# Sensor_Board.net
KiCad netlist of a schematic drawn in EAGLE
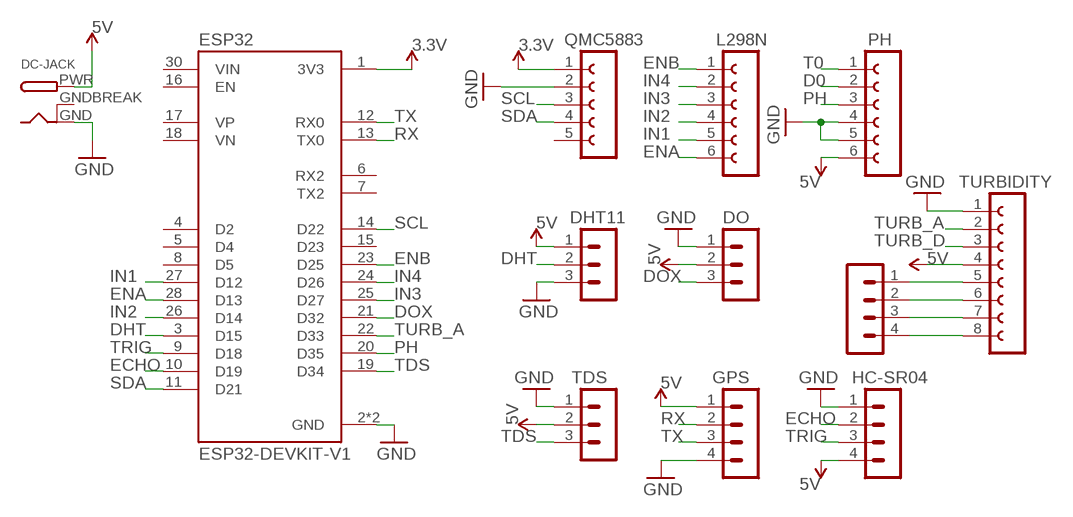
[diagram p0: schematic, sheet 1]

(export (version "E")
  (design (tool "Eeschema 10.0.6"))
  (components
    (comp (ref "DC-JACK")
      (value "DCBARRELPTH")
      (footprint "eagle-import:DCJACK_2MM_PTH")
      (libsource (lib "eagle-import") (part "DCBARRELPTH"))
    )
    (comp (ref "DHT11")
      (value "MA03-1")
      (footprint "eagle-import:MA03-1")
      (libsource (lib "eagle-import") (part "MA03-1"))
    )
    (comp (ref "DO")
      (value "MA03-1")
      (footprint "eagle-import:MA03-1")
      (libsource (lib "eagle-import") (part "MA03-1"))
    )
    (comp (ref "ESP32")
      (value "ESP32-DEVKIT-V1")
      (footprint "eagle-import:MODULE_ESP32_DEVKIT_V1")
      (fields (field (name "MF") "Do it"))
      (libsource (lib "eagle-import") (part "ESP32-DEVKIT-V1"))
    )
    (comp (ref "GPS")
      (value "MA04-1")
      (footprint "eagle-import:MA04-1")
      (libsource (lib "eagle-import") (part "MA04-1"))
    )
    (comp (ref "HC-SR04")
      (value "MA04-1")
      (footprint "eagle-import:MA04-1")
      (libsource (lib "eagle-import") (part "MA04-1"))
    )
    (comp (ref "L298N")
      (value "FE06-1")
      (footprint "eagle-import:FE06")
      (libsource (lib "eagle-import") (part "FE06-1"))
    )
    (comp (ref "PH")
      (value "FE06-1")
      (footprint "eagle-import:FE06")
      (libsource (lib "eagle-import") (part "FE06-1"))
    )
    (comp (ref "QMC5883")
      (value "FE05W")
      (footprint "eagle-import:FE05W")
      (libsource (lib "eagle-import") (part "FE05W"))
    )
    (comp (ref "SV10")
      (value "MA04-1")
      (footprint "eagle-import:MA04-1")
      (libsource (lib "eagle-import") (part "MA04-1"))
    )
    (comp (ref "TDS")
      (value "MA03-1")
      (footprint "eagle-import:MA03-1")
      (libsource (lib "eagle-import") (part "MA03-1"))
    )
    (comp (ref "TURBIDITY")
      (value "FE08-1")
      (footprint "eagle-import:FE08")
      (libsource (lib "eagle-import") (part "FE08-1"))
    )
  )
  (nets
    (net (code "1") (name "/D0") (class "Default")
      (node (ref "PH") (pin "2") (pinfunction "2_2") (pintype "passive"))
    )
    (net (code "2") (name "/DHT") (class "Default")
      (node (ref "DHT11") (pin "2") (pinfunction "2_2") (pintype "passive"))
      (node (ref "ESP32") (pin "3") (pinfunction "D15_3") (pintype "bidirectional"))
    )
    (net (code "3") (name "/DOX") (class "Default")
      (node (ref "DO") (pin "3") (pinfunction "3_3") (pintype "passive"))
      (node (ref "ESP32") (pin "21") (pinfunction "D32_21") (pintype "bidirectional"))
    )
    (net (code "4") (name "/ECHO") (class "Default")
      (node (ref "ESP32") (pin "10") (pinfunction "D19_10") (pintype "bidirectional"))
      (node (ref "HC-SR04") (pin "2") (pinfunction "2_2") (pintype "passive"))
    )
    (net (code "5") (name "/ENA") (class "Default")
      (node (ref "ESP32") (pin "28") (pinfunction "D13_28") (pintype "bidirectional"))
      (node (ref "L298N") (pin "6") (pinfunction "6_6") (pintype "passive"))
    )
    (net (code "6") (name "/ENB") (class "Default")
      (node (ref "ESP32") (pin "23") (pinfunction "D25_23") (pintype "bidirectional"))
      (node (ref "L298N") (pin "1") (pinfunction "1_1") (pintype "passive"))
    )
    (net (code "7") (name "/GNDBREAK") (class "Default")
      (node (ref "DC-JACK") (pin "GNDBREAK") (pinfunction "GNDBREAK_GNDBREAK") (pintype "power_in"))
    )
    (net (code "8") (name "/IN1") (class "Default")
      (node (ref "ESP32") (pin "27") (pinfunction "D12_27") (pintype "bidirectional"))
      (node (ref "L298N") (pin "5") (pinfunction "5_5") (pintype "passive"))
    )
    (net (code "9") (name "/IN2") (class "Default")
      (node (ref "ESP32") (pin "26") (pinfunction "D14_26") (pintype "bidirectional"))
      (node (ref "L298N") (pin "4") (pinfunction "4_4") (pintype "passive"))
    )
    (net (code "10") (name "/IN3") (class "Default")
      (node (ref "ESP32") (pin "25") (pinfunction "D27_25") (pintype "bidirectional"))
      (node (ref "L298N") (pin "3") (pinfunction "3_3") (pintype "passive"))
    )
    (net (code "11") (name "/IN4") (class "Default")
      (node (ref "ESP32") (pin "24") (pinfunction "D26_24") (pintype "bidirectional"))
      (node (ref "L298N") (pin "2") (pinfunction "2_2") (pintype "passive"))
    )
    (net (code "12") (name "/PH") (class "Default")
      (node (ref "ESP32") (pin "20") (pinfunction "D35_20") (pintype "bidirectional"))
      (node (ref "PH") (pin "3") (pinfunction "3_3") (pintype "passive"))
    )
    (net (code "13") (name "/RX") (class "Default")
      (node (ref "ESP32") (pin "13") (pinfunction "TX0_13") (pintype "output"))
      (node (ref "GPS") (pin "2") (pinfunction "2_2") (pintype "passive"))
    )
    (net (code "14") (name "/SCL") (class "Default")
      (node (ref "ESP32") (pin "14") (pinfunction "D22_14") (pintype "bidirectional"))
      (node (ref "QMC5883") (pin "3") (pinfunction "3_3") (pintype "passive"))
    )
    (net (code "15") (name "/SDA") (class "Default")
      (node (ref "ESP32") (pin "11") (pinfunction "D21_11") (pintype "bidirectional"))
      (node (ref "QMC5883") (pin "4") (pinfunction "4_4") (pintype "passive"))
    )
    (net (code "16") (name "/T0") (class "Default")
      (node (ref "PH") (pin "1") (pinfunction "1_1") (pintype "passive"))
    )
    (net (code "17") (name "/TDS") (class "Default")
      (node (ref "ESP32") (pin "19") (pinfunction "D34_19") (pintype "bidirectional"))
      (node (ref "TDS") (pin "3") (pinfunction "3_3") (pintype "passive"))
    )
    (net (code "18") (name "/TRIG") (class "Default")
      (node (ref "ESP32") (pin "9") (pinfunction "D18_9") (pintype "bidirectional"))
      (node (ref "HC-SR04") (pin "3") (pinfunction "3_3") (pintype "passive"))
    )
    (net (code "19") (name "/TURB_A") (class "Default")
      (node (ref "ESP32") (pin "22") (pinfunction "D33_22") (pintype "bidirectional"))
      (node (ref "TURBIDITY") (pin "2") (pinfunction "2_2") (pintype "passive"))
    )
    (net (code "20") (name "/TURB_D") (class "Default")
      (node (ref "TURBIDITY") (pin "3") (pinfunction "3_3") (pintype "passive"))
    )
    (net (code "21") (name "/TX") (class "Default")
      (node (ref "ESP32") (pin "12") (pinfunction "RX0_12") (pintype "input"))
      (node (ref "GPS") (pin "3") (pinfunction "3_3") (pintype "passive"))
    )
    (net (code "22") (name "GND") (class "Default")
      (node (ref "DC-JACK") (pin "GND") (pinfunction "GND_GND") (pintype "power_in"))
      (node (ref "DHT11") (pin "3") (pinfunction "3_3") (pintype "passive"))
      (node (ref "DO") (pin "1") (pinfunction "1_1") (pintype "passive"))
      (node (ref "ESP32") (pin "2") (pinfunction "GND_2") (pintype "power_in"))
      (node (ref "ESP32") (pin "29") (pinfunction "GND_29") (pintype "power_in"))
      (node (ref "GPS") (pin "4") (pinfunction "4_4") (pintype "passive"))
      (node (ref "HC-SR04") (pin "1") (pinfunction "1_1") (pintype "passive"))
      (node (ref "PH") (pin "4") (pinfunction "4_4") (pintype "passive"))
      (node (ref "PH") (pin "5") (pinfunction "5_5") (pintype "passive"))
      (node (ref "QMC5883") (pin "2") (pinfunction "2_2") (pintype "passive"))
      (node (ref "TDS") (pin "1") (pinfunction "1_1") (pintype "passive"))
      (node (ref "TURBIDITY") (pin "1") (pinfunction "1_1") (pintype "passive"))
    )
    (net (code "23") (name "Net-(SV10-Pad1)") (class "Default")
      (node (ref "SV10") (pin "1") (pinfunction "1_1") (pintype "passive"))
      (node (ref "TURBIDITY") (pin "5") (pinfunction "5_5") (pintype "passive"))
    )
    (net (code "24") (name "Net-(SV10-Pad2)") (class "Default")
      (node (ref "SV10") (pin "2") (pinfunction "2_2") (pintype "passive"))
      (node (ref "TURBIDITY") (pin "6") (pinfunction "6_6") (pintype "passive"))
    )
    (net (code "25") (name "Net-(SV10-Pad3)") (class "Default")
      (node (ref "SV10") (pin "3") (pinfunction "3_3") (pintype "passive"))
      (node (ref "TURBIDITY") (pin "7") (pinfunction "7_7") (pintype "passive"))
    )
    (net (code "26") (name "Net-(SV10-Pad4)") (class "Default")
      (node (ref "SV10") (pin "4") (pinfunction "4_4") (pintype "passive"))
      (node (ref "TURBIDITY") (pin "8") (pinfunction "8_8") (pintype "passive"))
    )
    (net (code "27") (name "VCC_1") (class "Default")
      (node (ref "DC-JACK") (pin "PWR") (pinfunction "PWR_PWR") (pintype "power_in"))
      (node (ref "DHT11") (pin "1") (pinfunction "1_1") (pintype "passive"))
      (node (ref "DO") (pin "2") (pinfunction "2_2") (pintype "passive"))
      (node (ref "GPS") (pin "1") (pinfunction "1_1") (pintype "passive"))
      (node (ref "HC-SR04") (pin "4") (pinfunction "4_4") (pintype "passive"))
      (node (ref "PH") (pin "6") (pinfunction "6_6") (pintype "passive"))
      (node (ref "TDS") (pin "2") (pinfunction "2_2") (pintype "passive"))
      (node (ref "TURBIDITY") (pin "4") (pinfunction "4_4") (pintype "passive"))
    )
    (net (code "28") (name "VCC_2") (class "Default")
      (node (ref "ESP32") (pin "1") (pinfunction "3V3_1") (pintype "output"))
      (node (ref "QMC5883") (pin "1") (pinfunction "1_1") (pintype "passive"))
    )
    (net (code "29") (name "unconnected-(ESP32-D2-Pad4)") (class "Default")
      (node (ref "ESP32") (pin "4") (pinfunction "D2_4") (pintype "bidirectional"))
    )
    (net (code "30") (name "unconnected-(ESP32-D4-Pad5)") (class "Default")
      (node (ref "ESP32") (pin "5") (pinfunction "D4_5") (pintype "bidirectional"))
    )
    (net (code "31") (name "unconnected-(ESP32-D5-Pad8)") (class "Default")
      (node (ref "ESP32") (pin "8") (pinfunction "D5_8") (pintype "bidirectional"))
    )
    (net (code "32") (name "unconnected-(ESP32-D23-Pad15)") (class "Default")
      (node (ref "ESP32") (pin "15") (pinfunction "D23_15") (pintype "bidirectional"))
    )
    (net (code "33") (name "unconnected-(ESP32-EN-Pad16)") (class "Default")
      (node (ref "ESP32") (pin "16") (pinfunction "EN_16") (pintype "input"))
    )
    (net (code "34") (name "unconnected-(ESP32-RX2-Pad6)") (class "Default")
      (node (ref "ESP32") (pin "6") (pinfunction "RX2_6") (pintype "input"))
    )
    (net (code "35") (name "unconnected-(ESP32-TX2-Pad7)") (class "Default")
      (node (ref "ESP32") (pin "7") (pinfunction "TX2_7") (pintype "output"))
    )
    (net (code "36") (name "unconnected-(ESP32-VIN-Pad30)") (class "Default")
      (node (ref "ESP32") (pin "30") (pinfunction "VIN_30") (pintype "input"))
    )
    (net (code "37") (name "unconnected-(ESP32-VN-Pad18)") (class "Default")
      (node (ref "ESP32") (pin "18") (pinfunction "VN_18") (pintype "bidirectional"))
    )
    (net (code "38") (name "unconnected-(ESP32-VP-Pad17)") (class "Default")
      (node (ref "ESP32") (pin "17") (pinfunction "VP_17") (pintype "bidirectional"))
    )
    (net (code "39") (name "unconnected-(QMC5883-Pad5)") (class "Default")
      (node (ref "QMC5883") (pin "5") (pinfunction "5_5") (pintype "passive"))
    )
  )
)
